# DAC.net
KiCad netlist of a schematic drawn in Altium Designer
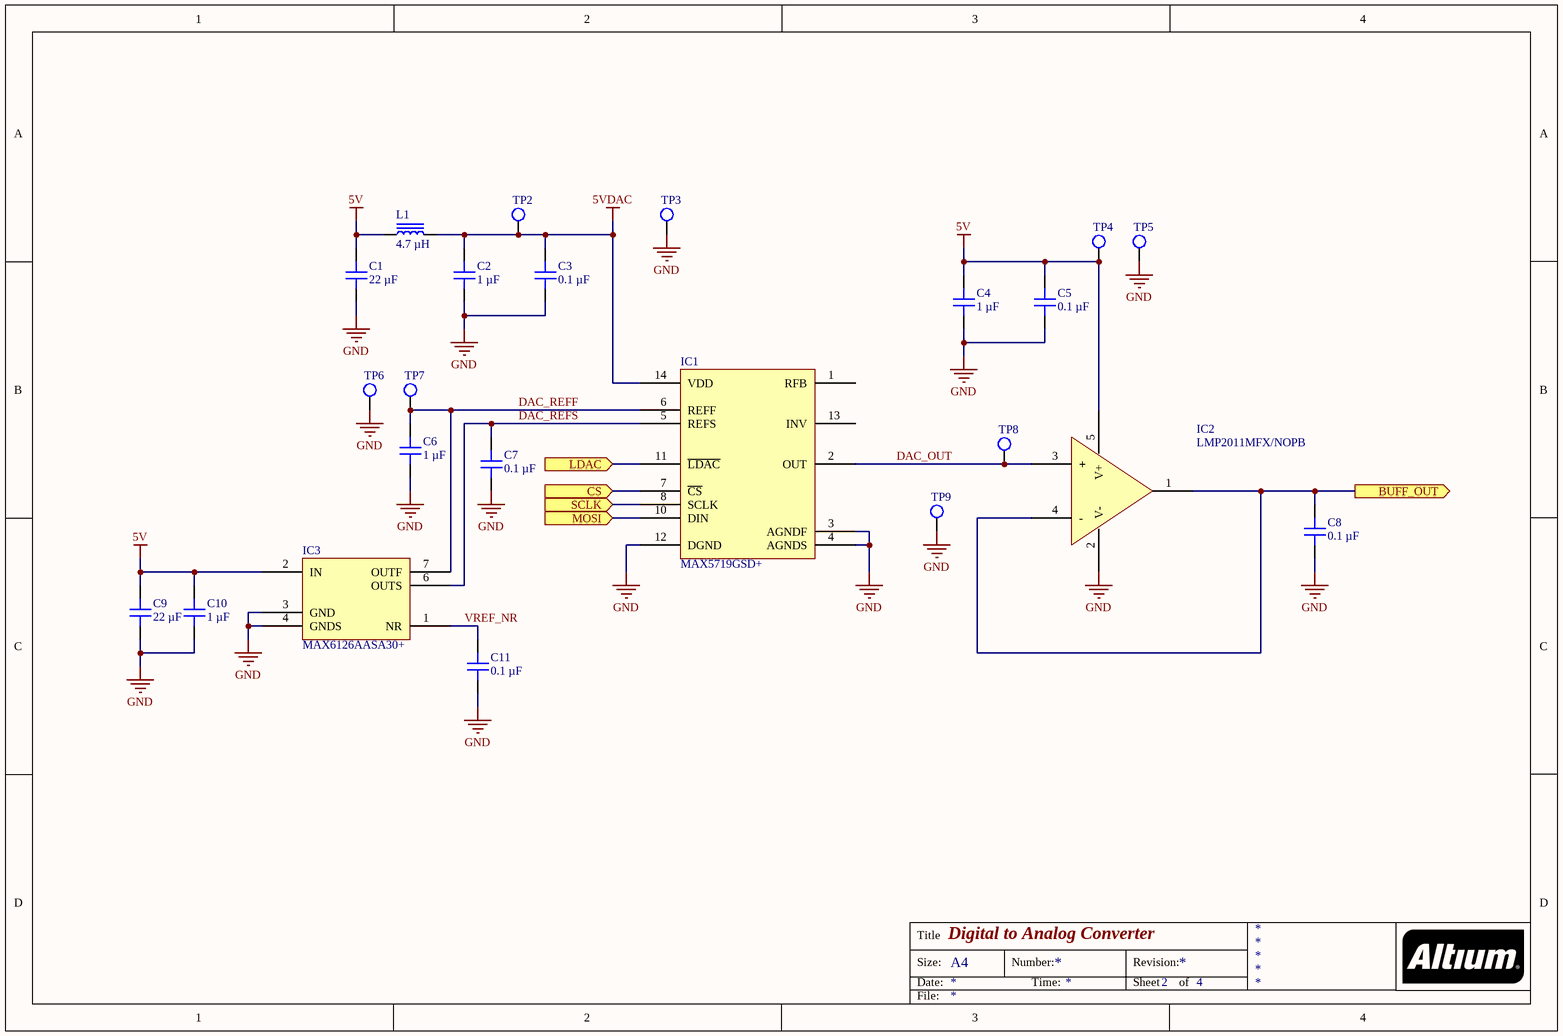
[diagram p0: DAC.SchDoc]

(export (version "E")
  (design (tool "Eeschema 10.0.6"))
  (components
    (comp (ref "C1")
      (value "22 µF")
      (footprint "CAP 0603_1608")
      (description "CAP CER 22UF 10V X5R 0603")
      (fields
        (field (name "PART NUMBER") "CL10A226MP8NUNE")
        (field (name "MANUFACTURER") "Samsung Electro-Mechanics")
      )
      (libsource (lib "altiumlibrary.com") (part "Capacitor"))
    )
    (comp (ref "C2")
      (value "1 µF")
      (footprint "CAP 0603_1608")
      (description "CAP CER 1UF 25V X7R 0603")
      (fields
        (field (name "PART NUMBER") "GCM188R71E105KA64D")
        (field (name "MANUFACTURER") "Murata Electronics")
      )
      (libsource (lib "altiumlibrary.com") (part "Capacitor"))
    )
    (comp (ref "C3")
      (value "0.1 µF")
      (footprint "CAP 0603_1608")
      (description "CAP CER 0.1UF 50V X7R 0603")
      (fields
        (field (name "PART NUMBER") "CL10B104KB8NNNC")
        (field (name "MANUFACTURER") "Samsung Electro-Mechanics")
      )
      (libsource (lib "altiumlibrary.com") (part "Capacitor"))
    )
    (comp (ref "C4")
      (value "1 µF")
      (footprint "CAP 0603_1608")
      (description "CAP CER 1UF 25V X7R 0603")
      (fields
        (field (name "PART NUMBER") "GCM188R71E105KA64D")
        (field (name "MANUFACTURER") "Murata Electronics")
      )
      (libsource (lib "altiumlibrary.com") (part "Capacitor"))
    )
    (comp (ref "C5")
      (value "0.1 µF")
      (footprint "CAP 0603_1608")
      (description "CAP CER 0.1UF 50V X7R 0603")
      (fields
        (field (name "PART NUMBER") "CL10B104KB8NNNC")
        (field (name "MANUFACTURER") "Samsung Electro-Mechanics")
      )
      (libsource (lib "altiumlibrary.com") (part "Capacitor"))
    )
    (comp (ref "C6")
      (value "1 µF")
      (footprint "CAP 0603_1608")
      (description "CAP CER 1UF 25V X7R 0603")
      (fields
        (field (name "PART NUMBER") "GCM188R71E105KA64D")
        (field (name "MANUFACTURER") "Murata Electronics")
      )
      (libsource (lib "altiumlibrary.com") (part "Capacitor"))
    )
    (comp (ref "C7")
      (value "0.1 µF")
      (footprint "CAP 0603_1608")
      (description "CAP CER 0.1UF 50V X7R 0603")
      (fields
        (field (name "PART NUMBER") "CL10B104KB8NNNC")
        (field (name "MANUFACTURER") "Samsung Electro-Mechanics")
      )
      (libsource (lib "altiumlibrary.com") (part "Capacitor"))
    )
    (comp (ref "C8")
      (value "0.1 µF")
      (footprint "CAP 0603_1608")
      (description "CAP CER 0.1UF 50V X7R 0603")
      (fields
        (field (name "PART NUMBER") "CL10B104KB8NNNC")
        (field (name "MANUFACTURER") "Samsung Electro-Mechanics")
      )
      (libsource (lib "altiumlibrary.com") (part "Capacitor"))
    )
    (comp (ref "C9")
      (value "22 µF")
      (footprint "CAP 0603_1608")
      (description "CAP CER 22UF 10V X5R 0603")
      (fields
        (field (name "PART NUMBER") "CL10A226MP8NUNE")
        (field (name "MANUFACTURER") "Samsung Electro-Mechanics")
      )
      (libsource (lib "altiumlibrary.com") (part "Capacitor"))
    )
    (comp (ref "C10")
      (value "1 µF")
      (footprint "CAP 0603_1608")
      (description "CAP CER 1UF 25V X7R 0603")
      (fields
        (field (name "PART NUMBER") "GCM188R71E105KA64D")
        (field (name "MANUFACTURER") "Murata Electronics")
      )
      (libsource (lib "altiumlibrary.com") (part "Capacitor"))
    )
    (comp (ref "C11")
      (value "0.1 µF")
      (footprint "CAP 0603_1608")
      (description "CAP CER 0.1UF 50V X7R 0603")
      (fields
        (field (name "PART NUMBER") "CL10B104KB8NNNC")
        (field (name "MANUFACTURER") "Samsung Electro-Mechanics")
      )
      (libsource (lib "altiumlibrary.com") (part "Capacitor"))
    )
    (comp (ref "IC1")
      (value "MAX5719GSD+")
      (footprint "AD SOIC-14 S14+4")
      (description "IC DAC 20BIT V-OUT 14SOIC")
      (fields (field (name "MANUFACTURER") "Analog Devices Inc./Maxim Integrated"))
      (libsource (lib "altiumlibrary.com") (part "AD MAX5719GSD"))
    )
    (comp (ref "IC2")
      (value "LMP2011MFX/NOPB")
      (footprint "TI SOT-23-5 DBV")
      (description "IC OPAMP GP 1 CIRCUIT SOT23-5")
      (fields (field (name "MANUFACTURER") "Texas Instruments"))
      (libsource (lib "altiumlibrary.com") (part "TI LMP2011MF DBV"))
    )
    (comp (ref "IC3")
      (value "MAX6126AASA30+")
      (footprint "AD SOIC-8 S8+4")
      (description "IC VREF SERIES 0.02% 8SOIC")
      (fields (field (name "MANUFACTURER") "Maxim Integrated") (field (name "TOLERANCE") "±0.02%"))
      (libsource (lib "altiumlibrary.com") (part "MAXIM MAX6126"))
    )
    (comp (ref "L1")
      (value "4.7 µH")
      (footprint "WURTH WE-LQS 3015")
      (description "FIXED IND 4.7UH 1.3A 96 MOHM SMD")
      (fields (field (name "PART NUMBER") "74404032047") (field (name "MANUFACTURER") "Würth Elektronik"))
      (libsource (lib "altiumlibrary.com") (part "Inductor"))
    )
    (comp (ref "TP2")
      (value "Test Point")
      (footprint "TestPoint-1.5mm")
      (libsource (lib "Original Circuit") (part "Test Point"))
    )
    (comp (ref "TP3")
      (value "Test Point")
      (footprint "TestPoint-1.5mm")
      (libsource (lib "Original Circuit") (part "Test Point"))
    )
    (comp (ref "TP4")
      (value "Test Point")
      (footprint "TestPoint-1.5mm")
      (libsource (lib "Original Circuit") (part "Test Point"))
    )
    (comp (ref "TP5")
      (value "Test Point")
      (footprint "TestPoint-1.5mm")
      (libsource (lib "Original Circuit") (part "Test Point"))
    )
    (comp (ref "TP6")
      (value "Test Point")
      (footprint "TestPoint-1.5mm")
      (libsource (lib "Original Circuit") (part "Test Point"))
    )
    (comp (ref "TP7")
      (value "Test Point")
      (footprint "TestPoint-1.5mm")
      (libsource (lib "Original Circuit") (part "Test Point"))
    )
    (comp (ref "TP8")
      (value "Test Point")
      (footprint "TestPoint-1.5mm")
      (libsource (lib "Original Circuit") (part "Test Point"))
    )
    (comp (ref "TP9")
      (value "Test Point")
      (footprint "TestPoint-1.5mm")
      (libsource (lib "Original Circuit") (part "Test Point"))
    )
  )
  (nets
    (net (code "1") (name "/BUFF_OUT") (class "Default")
      (node (ref "C8") (pin "1") (pinfunction "1_1") (pintype "passive"))
      (node (ref "IC2") (pin "1") (pinfunction "OUT_1") (pintype "passive"))
      (node (ref "IC2") (pin "4") (pinfunction "-_4") (pintype "passive"))
    )
    (net (code "2") (name "/CS") (class "Default")
      (node (ref "IC1") (pin "7") (pinfunction "~{CS}_7") (pintype "passive"))
    )
    (net (code "3") (name "/DAC_OUT") (class "Default")
      (node (ref "IC1") (pin "2") (pinfunction "OUT_2") (pintype "passive"))
      (node (ref "IC2") (pin "3") (pinfunction "+_3") (pintype "passive"))
      (node (ref "TP8") (pin "1") (pinfunction "TP_1") (pintype "passive"))
    )
    (net (code "4") (name "/DAC_REFF") (class "Default")
      (node (ref "C6") (pin "2") (pinfunction "2_2") (pintype "passive"))
      (node (ref "IC1") (pin "6") (pinfunction "REFF_6") (pintype "passive"))
      (node (ref "IC3") (pin "7") (pinfunction "OUTF_7") (pintype "passive"))
      (node (ref "TP7") (pin "1") (pinfunction "TP_1") (pintype "passive"))
    )
    (net (code "5") (name "/DAC_REFS") (class "Default")
      (node (ref "C7") (pin "1") (pinfunction "1_1") (pintype "passive"))
      (node (ref "IC1") (pin "5") (pinfunction "REFS_5") (pintype "passive"))
      (node (ref "IC3") (pin "6") (pinfunction "OUTS_6") (pintype "passive"))
    )
    (net (code "6") (name "/LDAC") (class "Default")
      (node (ref "IC1") (pin "11") (pinfunction "~{LDAC}_11") (pintype "passive"))
    )
    (net (code "7") (name "/MOSI") (class "Default")
      (node (ref "IC1") (pin "10") (pinfunction "DIN_10") (pintype "passive"))
    )
    (net (code "8") (name "/SCLK") (class "Default")
      (node (ref "IC1") (pin "8") (pinfunction "SCLK_8") (pintype "passive"))
    )
    (net (code "9") (name "/VREF_NR") (class "Default")
      (node (ref "C11") (pin "1") (pinfunction "1_1") (pintype "passive"))
      (node (ref "IC3") (pin "1") (pinfunction "NR_1") (pintype "passive"))
    )
    (net (code "10") (name "5V") (class "Default")
      (node (ref "C1") (pin "2") (pinfunction "2_2") (pintype "passive"))
      (node (ref "C10") (pin "2") (pinfunction "2_2") (pintype "passive"))
      (node (ref "C4") (pin "2") (pinfunction "2_2") (pintype "passive"))
      (node (ref "C5") (pin "1") (pinfunction "1_1") (pintype "passive"))
      (node (ref "C9") (pin "2") (pinfunction "2_2") (pintype "passive"))
      (node (ref "IC2") (pin "5") (pinfunction "V+_5") (pintype "passive"))
      (node (ref "IC3") (pin "2") (pinfunction "IN_2") (pintype "passive"))
      (node (ref "L1") (pin "1") (pinfunction "1_1") (pintype "passive"))
      (node (ref "TP4") (pin "1") (pinfunction "TP_1") (pintype "passive"))
    )
    (net (code "11") (name "5VDAC") (class "Default")
      (node (ref "C2") (pin "2") (pinfunction "2_2") (pintype "passive"))
      (node (ref "C3") (pin "1") (pinfunction "1_1") (pintype "passive"))
      (node (ref "IC1") (pin "14") (pinfunction "VDD_14") (pintype "passive"))
      (node (ref "L1") (pin "2") (pinfunction "2_2") (pintype "passive"))
      (node (ref "TP2") (pin "1") (pinfunction "TP_1") (pintype "passive"))
    )
    (net (code "12") (name "GND") (class "Default")
      (node (ref "C1") (pin "1") (pinfunction "1_1") (pintype "passive"))
      (node (ref "C10") (pin "1") (pinfunction "1_1") (pintype "passive"))
      (node (ref "C11") (pin "2") (pinfunction "2_2") (pintype "passive"))
      (node (ref "C2") (pin "1") (pinfunction "1_1") (pintype "passive"))
      (node (ref "C3") (pin "2") (pinfunction "2_2") (pintype "passive"))
      (node (ref "C4") (pin "1") (pinfunction "1_1") (pintype "passive"))
      (node (ref "C5") (pin "2") (pinfunction "2_2") (pintype "passive"))
      (node (ref "C6") (pin "1") (pinfunction "1_1") (pintype "passive"))
      (node (ref "C7") (pin "2") (pinfunction "2_2") (pintype "passive"))
      (node (ref "C8") (pin "2") (pinfunction "2_2") (pintype "passive"))
      (node (ref "C9") (pin "1") (pinfunction "1_1") (pintype "passive"))
      (node (ref "IC1") (pin "12") (pinfunction "DGND_12") (pintype "passive"))
      (node (ref "IC1") (pin "3") (pinfunction "AGNDF_3") (pintype "passive"))
      (node (ref "IC1") (pin "4") (pinfunction "AGNDS_4") (pintype "passive"))
      (node (ref "IC2") (pin "2") (pinfunction "V-_2") (pintype "passive"))
      (node (ref "IC3") (pin "3") (pinfunction "GND_3") (pintype "passive"))
      (node (ref "IC3") (pin "4") (pinfunction "GNDS_4") (pintype "passive"))
      (node (ref "TP3") (pin "1") (pinfunction "TP_1") (pintype "passive"))
      (node (ref "TP5") (pin "1") (pinfunction "TP_1") (pintype "passive"))
      (node (ref "TP6") (pin "1") (pinfunction "TP_1") (pintype "passive"))
      (node (ref "TP9") (pin "1") (pinfunction "TP_1") (pintype "passive"))
    )
    (net (code "13") (name "unconnected-(IC1-INV-Pad13)") (class "Default")
      (node (ref "IC1") (pin "13") (pinfunction "INV_13") (pintype "passive"))
    )
    (net (code "14") (name "unconnected-(IC1-RFB-Pad1)") (class "Default")
      (node (ref "IC1") (pin "1") (pinfunction "RFB_1") (pintype "passive"))
    )
  )
)
